# ATmega.net
KiCad netlist of a schematic drawn in Altium Designer
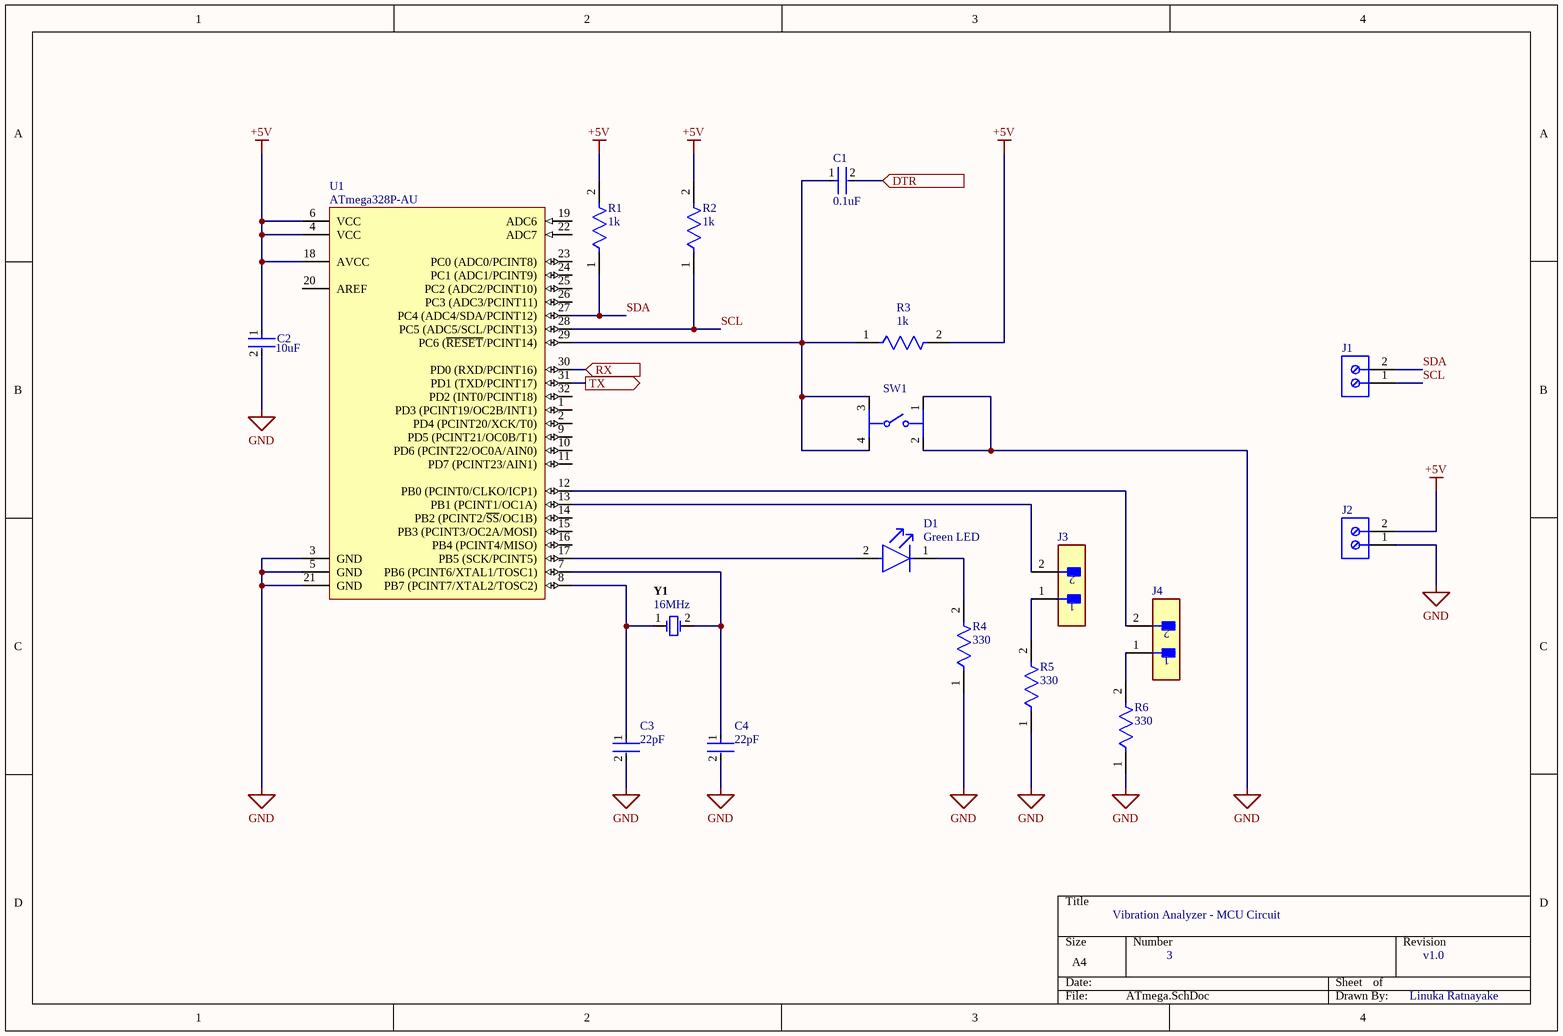
[diagram p0: ATmega.SchDoc]

(export (version "E")
  (design (tool "Eeschema 10.0.6"))
  (components
    (comp (ref "C1")
      (value "GRM31M1X1H104JA01L")
      (footprint "FP-GRM31M-0_15-IPC_A")
      (fields
        (field (name "VOLTAGE") "50V")
        (field (name "TOLERANCE") "5%")
        (field (name "CAPACITANCE") "0.1uF")
      )
      (libsource (lib "Altium Content Vault") (part "b4654b650e69147ec39a6b967a45e02"))
    )
    (comp (ref "C2")
      (value "GRM31M1X1H104JA01L")
      (footprint "FP-GRM31M-0_15-IPC_A")
      (fields
        (field (name "VOLTAGE") "50V")
        (field (name "TOLERANCE") "5%")
        (field (name "CAPACITANCE") "10uF")
      )
      (libsource (lib "Altium Content Vault") (part "b4654b650e69147ec39a6b967a45e02"))
    )
    (comp (ref "C3")
      (value "GRM31M1X1H104JA01L")
      (footprint "FP-GRM31M-0_15-IPC_A")
      (fields
        (field (name "VOLTAGE") "50V")
        (field (name "TOLERANCE") "5%")
        (field (name "CAPACITANCE") "22pF")
      )
      (libsource (lib "Altium Content Vault") (part "b4654b650e69147ec39a6b967a45e02"))
    )
    (comp (ref "C4")
      (value "GRM31M1X1H104JA01L")
      (footprint "FP-GRM31M-0_15-IPC_A")
      (fields
        (field (name "VOLTAGE") "50V")
        (field (name "TOLERANCE") "5%")
        (field (name "CAPACITANCE") "22pF")
      )
      (libsource (lib "Altium Content Vault") (part "b4654b650e69147ec39a6b967a45e02"))
    )
    (comp (ref "D1")
      (value "HSMG-C150")
      (footprint "FP-HSMG-C150-MFG")
      (description "LED GREEN DIFFUSED 1206 SMD")
      (fields
        (field (name "MANUFACTURER") "Broadcom")
        (field (name "OCTOPART") "https://octopart.com/hsmg-c150-broadcom-71131304")
        (field (name "COLOR") "Green LED")
      )
      (libsource (lib "Altium Content Vault") (part "8706943c75ba83719d021d2fdc84c58"))
    )
    (comp (ref "J1")
      (value "691214110002")
      (footprint "691214110002")
      (fields (field (name "VOLTAGE") "300V"))
      (libsource (lib "Altium Content Vault") (part "TBL - 1R - 02P - Screw"))
    )
    (comp (ref "J2")
      (value "691214110002")
      (footprint "691214110002")
      (fields (field (name "VOLTAGE") "300V"))
      (libsource (lib "Altium Content Vault") (part "TBL - 1R - 02P - Screw"))
    )
    (comp (ref "J3")
      (value "B2B-XH-A(LF)(SN)")
      (footprint "FP-B2B-XH-A_LF_SN-MFG")
      (description "CONN HEADER VERT 2POS 2.5MM")
      (libsource (lib "Altium Content Vault") (part "3bc925449376181038e59eaffc5286c"))
    )
    (comp (ref "J4")
      (value "B2B-XH-A(LF)(SN)")
      (footprint "FP-B2B-XH-A_LF_SN-MFG")
      (description "CONN HEADER VERT 2POS 2.5MM")
      (libsource (lib "Altium Content Vault") (part "3bc925449376181038e59eaffc5286c"))
    )
    (comp (ref "R1")
      (value "MCR18EZPF30R0")
      (footprint "FP-MCR18-IPC_B")
      (description "Thick Film Chip Resistor, 1206, 30Ω, 1%, 100ppm/°C, 0.25W, 200V")
      (fields (field (name "RESISTANCE") "1k") (field (name "TOLERANCE") "1%"))
      (libsource (lib "Altium Content Vault") (part "1029c3af85768c4190bb7ad29bc67b5"))
    )
    (comp (ref "R2")
      (value "MCR18EZPF30R0")
      (footprint "FP-MCR18-IPC_B")
      (description "Thick Film Chip Resistor, 1206, 30Ω, 1%, 100ppm/°C, 0.25W, 200V")
      (fields (field (name "RESISTANCE") "1k") (field (name "TOLERANCE") "1%"))
      (libsource (lib "Altium Content Vault") (part "1029c3af85768c4190bb7ad29bc67b5"))
    )
    (comp (ref "R3")
      (value "MCR18EZPF30R0")
      (footprint "FP-MCR18-IPC_B")
      (description "Thick Film Chip Resistor, 1206, 30Ω, 1%, 100ppm/°C, 0.25W, 200V")
      (fields (field (name "RESISTANCE") "1k") (field (name "TOLERANCE") "1%"))
      (libsource (lib "Altium Content Vault") (part "1029c3af85768c4190bb7ad29bc67b5"))
    )
    (comp (ref "R4")
      (value "MCR18EZPF30R0")
      (footprint "FP-MCR18-IPC_B")
      (description "Thick Film Chip Resistor, 1206, 30Ω, 1%, 100ppm/°C, 0.25W, 200V")
      (fields (field (name "RESISTANCE") "330") (field (name "TOLERANCE") "1%"))
      (libsource (lib "Altium Content Vault") (part "1029c3af85768c4190bb7ad29bc67b5"))
    )
    (comp (ref "R5")
      (value "MCR18EZPF30R0")
      (footprint "FP-MCR18-IPC_B")
      (description "Thick Film Chip Resistor, 1206, 30Ω, 1%, 100ppm/°C, 0.25W, 200V")
      (fields (field (name "RESISTANCE") "330") (field (name "TOLERANCE") "1%"))
      (libsource (lib "Altium Content Vault") (part "1029c3af85768c4190bb7ad29bc67b5"))
    )
    (comp (ref "R6")
      (value "MCR18EZPF30R0")
      (footprint "FP-MCR18-IPC_B")
      (description "Thick Film Chip Resistor, 1206, 30Ω, 1%, 100ppm/°C, 0.25W, 200V")
      (fields (field (name "RESISTANCE") "330") (field (name "TOLERANCE") "1%"))
      (libsource (lib "Altium Content Vault") (part "1029c3af85768c4190bb7ad29bc67b5"))
    )
    (comp (ref "SW1")
      (value "PTS645SM43SMTR92LFS")
      (footprint "FP-PTS645SM43SMTR92LFS-MFG")
      (description "SWITCH TACTILE SPST-NO 0.05A 12V")
      (libsource (lib "Altium Content Vault") (part "1adf0dd01260c80cf25a44bfd6b99ba"))
    )
    (comp (ref "U1")
      (value "ATmega328P-AU")
      (footprint "32A_M")
      (libsource (lib "Altium Content Vault") (part "MC-8B-ATM48-SQ32"))
    )
    (comp (ref "Y1")
      (value "FOXSLF/160-20")
      (footprint "FOX-FOXSLF160-20")
      (description "Resistance Weld Thru-Hole Crystal, 16 MHz, -20 to 70 degC, 2-Pin THD, RoHS, Bulk")
      (fields (field (name "TOLERANCE") "1%") (field (name "FREQUENCY") "16MHz"))
      (libsource (lib "Altium Content Vault") (part "XTAL-1-2-2"))
    )
  )
  (nets
    (net (code "1") (name "+5V") (class "Default")
      (node (ref "C2") (pin "1") (pinfunction "1_1") (pintype "passive"))
      (node (ref "J2") (pin "2") (pinfunction "2_2") (pintype "passive"))
      (node (ref "R1") (pin "2") (pinfunction "2_2") (pintype "passive"))
      (node (ref "R2") (pin "2") (pinfunction "2_2") (pintype "passive"))
      (node (ref "R3") (pin "2") (pinfunction "2_2") (pintype "passive"))
      (node (ref "U1") (pin "18") (pinfunction "AVCC_18") (pintype "power_in"))
      (node (ref "U1") (pin "4") (pinfunction "VCC_4") (pintype "power_in"))
      (node (ref "U1") (pin "6") (pinfunction "VCC_6") (pintype "power_in"))
    )
    (net (code "2") (name "/DTR") (class "Default")
      (node (ref "C1") (pin "2") (pinfunction "2_2") (pintype "passive"))
    )
    (net (code "3") (name "/RX") (class "Default")
      (node (ref "U1") (pin "30") (pinfunction "PD0_(RXD/PCINT16)_30") (pintype "bidirectional"))
    )
    (net (code "4") (name "/SCL") (class "Default")
      (node (ref "J1") (pin "1") (pinfunction "1_1") (pintype "passive"))
      (node (ref "R2") (pin "1") (pinfunction "1_1") (pintype "passive"))
      (node (ref "U1") (pin "28") (pinfunction "PC5_(ADC5/SCL/PCINT13)_28") (pintype "bidirectional"))
    )
    (net (code "5") (name "/SDA") (class "Default")
      (node (ref "J1") (pin "2") (pinfunction "2_2") (pintype "passive"))
      (node (ref "R1") (pin "1") (pinfunction "1_1") (pintype "passive"))
      (node (ref "U1") (pin "27") (pinfunction "PC4_(ADC4/SDA/PCINT12)_27") (pintype "bidirectional"))
    )
    (net (code "6") (name "/TX") (class "Default")
      (node (ref "U1") (pin "31") (pinfunction "PD1_(TXD/PCINT17)_31") (pintype "bidirectional"))
    )
    (net (code "7") (name "GND") (class "Default")
      (node (ref "C2") (pin "2") (pinfunction "2_2") (pintype "passive"))
      (node (ref "C3") (pin "2") (pinfunction "2_2") (pintype "passive"))
      (node (ref "C4") (pin "2") (pinfunction "2_2") (pintype "passive"))
      (node (ref "J2") (pin "1") (pinfunction "1_1") (pintype "passive"))
      (node (ref "R4") (pin "1") (pinfunction "1_1") (pintype "passive"))
      (node (ref "R5") (pin "1") (pinfunction "1_1") (pintype "passive"))
      (node (ref "R6") (pin "1") (pinfunction "1_1") (pintype "passive"))
      (node (ref "SW1") (pin "1") (pinfunction "1_1") (pintype "passive"))
      (node (ref "SW1") (pin "2") (pinfunction "2_2") (pintype "passive"))
      (node (ref "U1") (pin "21") (pinfunction "GND_21") (pintype "power_in"))
      (node (ref "U1") (pin "3") (pinfunction "GND_3") (pintype "power_in"))
      (node (ref "U1") (pin "5") (pinfunction "GND_5") (pintype "power_in"))
    )
    (net (code "8") (name "Net-(D1-A)") (class "Default")
      (node (ref "D1") (pin "2") (pinfunction "A_2") (pintype "passive"))
      (node (ref "U1") (pin "17") (pinfunction "PB5_(SCK/PCINT5)_17") (pintype "bidirectional"))
    )
    (net (code "9") (name "Net-(D1-C)") (class "Default")
      (node (ref "D1") (pin "1") (pinfunction "C_1") (pintype "passive"))
      (node (ref "R4") (pin "2") (pinfunction "2_2") (pintype "passive"))
    )
    (net (code "10") (name "Net-(J3-Pad1)") (class "Default")
      (node (ref "J3") (pin "1") (pinfunction "1_1") (pintype "passive"))
      (node (ref "R5") (pin "2") (pinfunction "2_2") (pintype "passive"))
    )
    (net (code "11") (name "Net-(J4-Pad1)") (class "Default")
      (node (ref "J4") (pin "1") (pinfunction "1_1") (pintype "passive"))
      (node (ref "R6") (pin "2") (pinfunction "2_2") (pintype "passive"))
    )
    (net (code "12") (name "Net-(U1-PB0_(PCINT0{slash}CLKO{slash}ICP1))") (class "Default")
      (node (ref "J4") (pin "2") (pinfunction "2_2") (pintype "passive"))
      (node (ref "U1") (pin "12") (pinfunction "PB0_(PCINT0/CLKO/ICP1)_12") (pintype "bidirectional"))
    )
    (net (code "13") (name "Net-(U1-PB1_(PCINT1{slash}OC1A))") (class "Default")
      (node (ref "J3") (pin "2") (pinfunction "2_2") (pintype "passive"))
      (node (ref "U1") (pin "13") (pinfunction "PB1_(PCINT1/OC1A)_13") (pintype "bidirectional"))
    )
    (net (code "14") (name "Net-(U1-PB6_(PCINT6{slash}XTAL1{slash}TOSC1))") (class "Default")
      (node (ref "C4") (pin "1") (pinfunction "1_1") (pintype "passive"))
      (node (ref "U1") (pin "7") (pinfunction "PB6_(PCINT6/XTAL1/TOSC1)_7") (pintype "bidirectional"))
      (node (ref "Y1") (pin "2") (pinfunction "2_2") (pintype "passive"))
    )
    (net (code "15") (name "Net-(U1-PB7_(PCINT7{slash}XTAL2{slash}TOSC2))") (class "Default")
      (node (ref "C3") (pin "1") (pinfunction "1_1") (pintype "passive"))
      (node (ref "U1") (pin "8") (pinfunction "PB7_(PCINT7/XTAL2/TOSC2)_8") (pintype "bidirectional"))
      (node (ref "Y1") (pin "1") (pinfunction "1_1") (pintype "passive"))
    )
    (net (code "16") (name "Net-(U1-PC6_(~{RESET}{slash}PCINT14))") (class "Default")
      (node (ref "C1") (pin "1") (pinfunction "1_1") (pintype "passive"))
      (node (ref "R3") (pin "1") (pinfunction "1_1") (pintype "passive"))
      (node (ref "SW1") (pin "3") (pinfunction "3_3") (pintype "passive"))
      (node (ref "SW1") (pin "4") (pinfunction "4_4") (pintype "passive"))
      (node (ref "U1") (pin "29") (pinfunction "PC6_(~{RESET}/PCINT14)_29") (pintype "bidirectional"))
    )
    (net (code "17") (name "unconnected-(U1-ADC6-Pad19)") (class "Default")
      (node (ref "U1") (pin "19") (pinfunction "ADC6_19") (pintype "input"))
    )
    (net (code "18") (name "unconnected-(U1-ADC7-Pad22)") (class "Default")
      (node (ref "U1") (pin "22") (pinfunction "ADC7_22") (pintype "input"))
    )
    (net (code "19") (name "unconnected-(U1-AREF-Pad20)") (class "Default")
      (node (ref "U1") (pin "20") (pinfunction "AREF_20") (pintype "passive"))
    )
    (net (code "20") (name "unconnected-(U1-PB2_(PCINT2{slash}~{SS}{slash}OC1B)-Pad14)") (class "Default")
      (node (ref "U1") (pin "14") (pinfunction "PB2_(PCINT2/~{SS}/OC1B)_14") (pintype "bidirectional"))
    )
    (net (code "21") (name "unconnected-(U1-PB3_(PCINT3{slash}OC2A{slash}MOSI)-Pad15)") (class "Default")
      (node (ref "U1") (pin "15") (pinfunction "PB3_(PCINT3/OC2A/MOSI)_15") (pintype "bidirectional"))
    )
    (net (code "22") (name "unconnected-(U1-PB4_(PCINT4{slash}MISO)-Pad16)") (class "Default")
      (node (ref "U1") (pin "16") (pinfunction "PB4_(PCINT4/MISO)_16") (pintype "bidirectional"))
    )
    (net (code "23") (name "unconnected-(U1-PC0_(ADC0{slash}PCINT8)-Pad23)") (class "Default")
      (node (ref "U1") (pin "23") (pinfunction "PC0_(ADC0/PCINT8)_23") (pintype "bidirectional"))
    )
    (net (code "24") (name "unconnected-(U1-PC1_(ADC1{slash}PCINT9)-Pad24)") (class "Default")
      (node (ref "U1") (pin "24") (pinfunction "PC1_(ADC1/PCINT9)_24") (pintype "bidirectional"))
    )
    (net (code "25") (name "unconnected-(U1-PC2_(ADC2{slash}PCINT10)-Pad25)") (class "Default")
      (node (ref "U1") (pin "25") (pinfunction "PC2_(ADC2/PCINT10)_25") (pintype "bidirectional"))
    )
    (net (code "26") (name "unconnected-(U1-PC3_(ADC3{slash}PCINT11)-Pad26)") (class "Default")
      (node (ref "U1") (pin "26") (pinfunction "PC3_(ADC3/PCINT11)_26") (pintype "bidirectional"))
    )
    (net (code "27") (name "unconnected-(U1-PD2_(INT0{slash}PCINT18)-Pad32)") (class "Default")
      (node (ref "U1") (pin "32") (pinfunction "PD2_(INT0/PCINT18)_32") (pintype "bidirectional"))
    )
    (net (code "28") (name "unconnected-(U1-PD3_(PCINT19{slash}OC2B{slash}INT1)-Pad1)") (class "Default")
      (node (ref "U1") (pin "1") (pinfunction "PD3_(PCINT19/OC2B/INT1)_1") (pintype "bidirectional"))
    )
    (net (code "29") (name "unconnected-(U1-PD4_(PCINT20{slash}XCK{slash}T0)-Pad2)") (class "Default")
      (node (ref "U1") (pin "2") (pinfunction "PD4_(PCINT20/XCK/T0)_2") (pintype "bidirectional"))
    )
    (net (code "30") (name "unconnected-(U1-PD5_(PCINT21{slash}OC0B{slash}T1)-Pad9)") (class "Default")
      (node (ref "U1") (pin "9") (pinfunction "PD5_(PCINT21/OC0B/T1)_9") (pintype "bidirectional"))
    )
    (net (code "31") (name "unconnected-(U1-PD6_(PCINT22{slash}OC0A{slash}AIN0)-Pad10)") (class "Default")
      (node (ref "U1") (pin "10") (pinfunction "PD6_(PCINT22/OC0A/AIN0)_10") (pintype "bidirectional"))
    )
    (net (code "32") (name "unconnected-(U1-PD7_(PCINT23{slash}AIN1)-Pad11)") (class "Default")
      (node (ref "U1") (pin "11") (pinfunction "PD7_(PCINT23/AIN1)_11") (pintype "bidirectional"))
    )
  )
)
